# EDU_High-Speed-Design_Power_3V3_1V375.net
KiCad netlist of a schematic drawn in Altium Designer
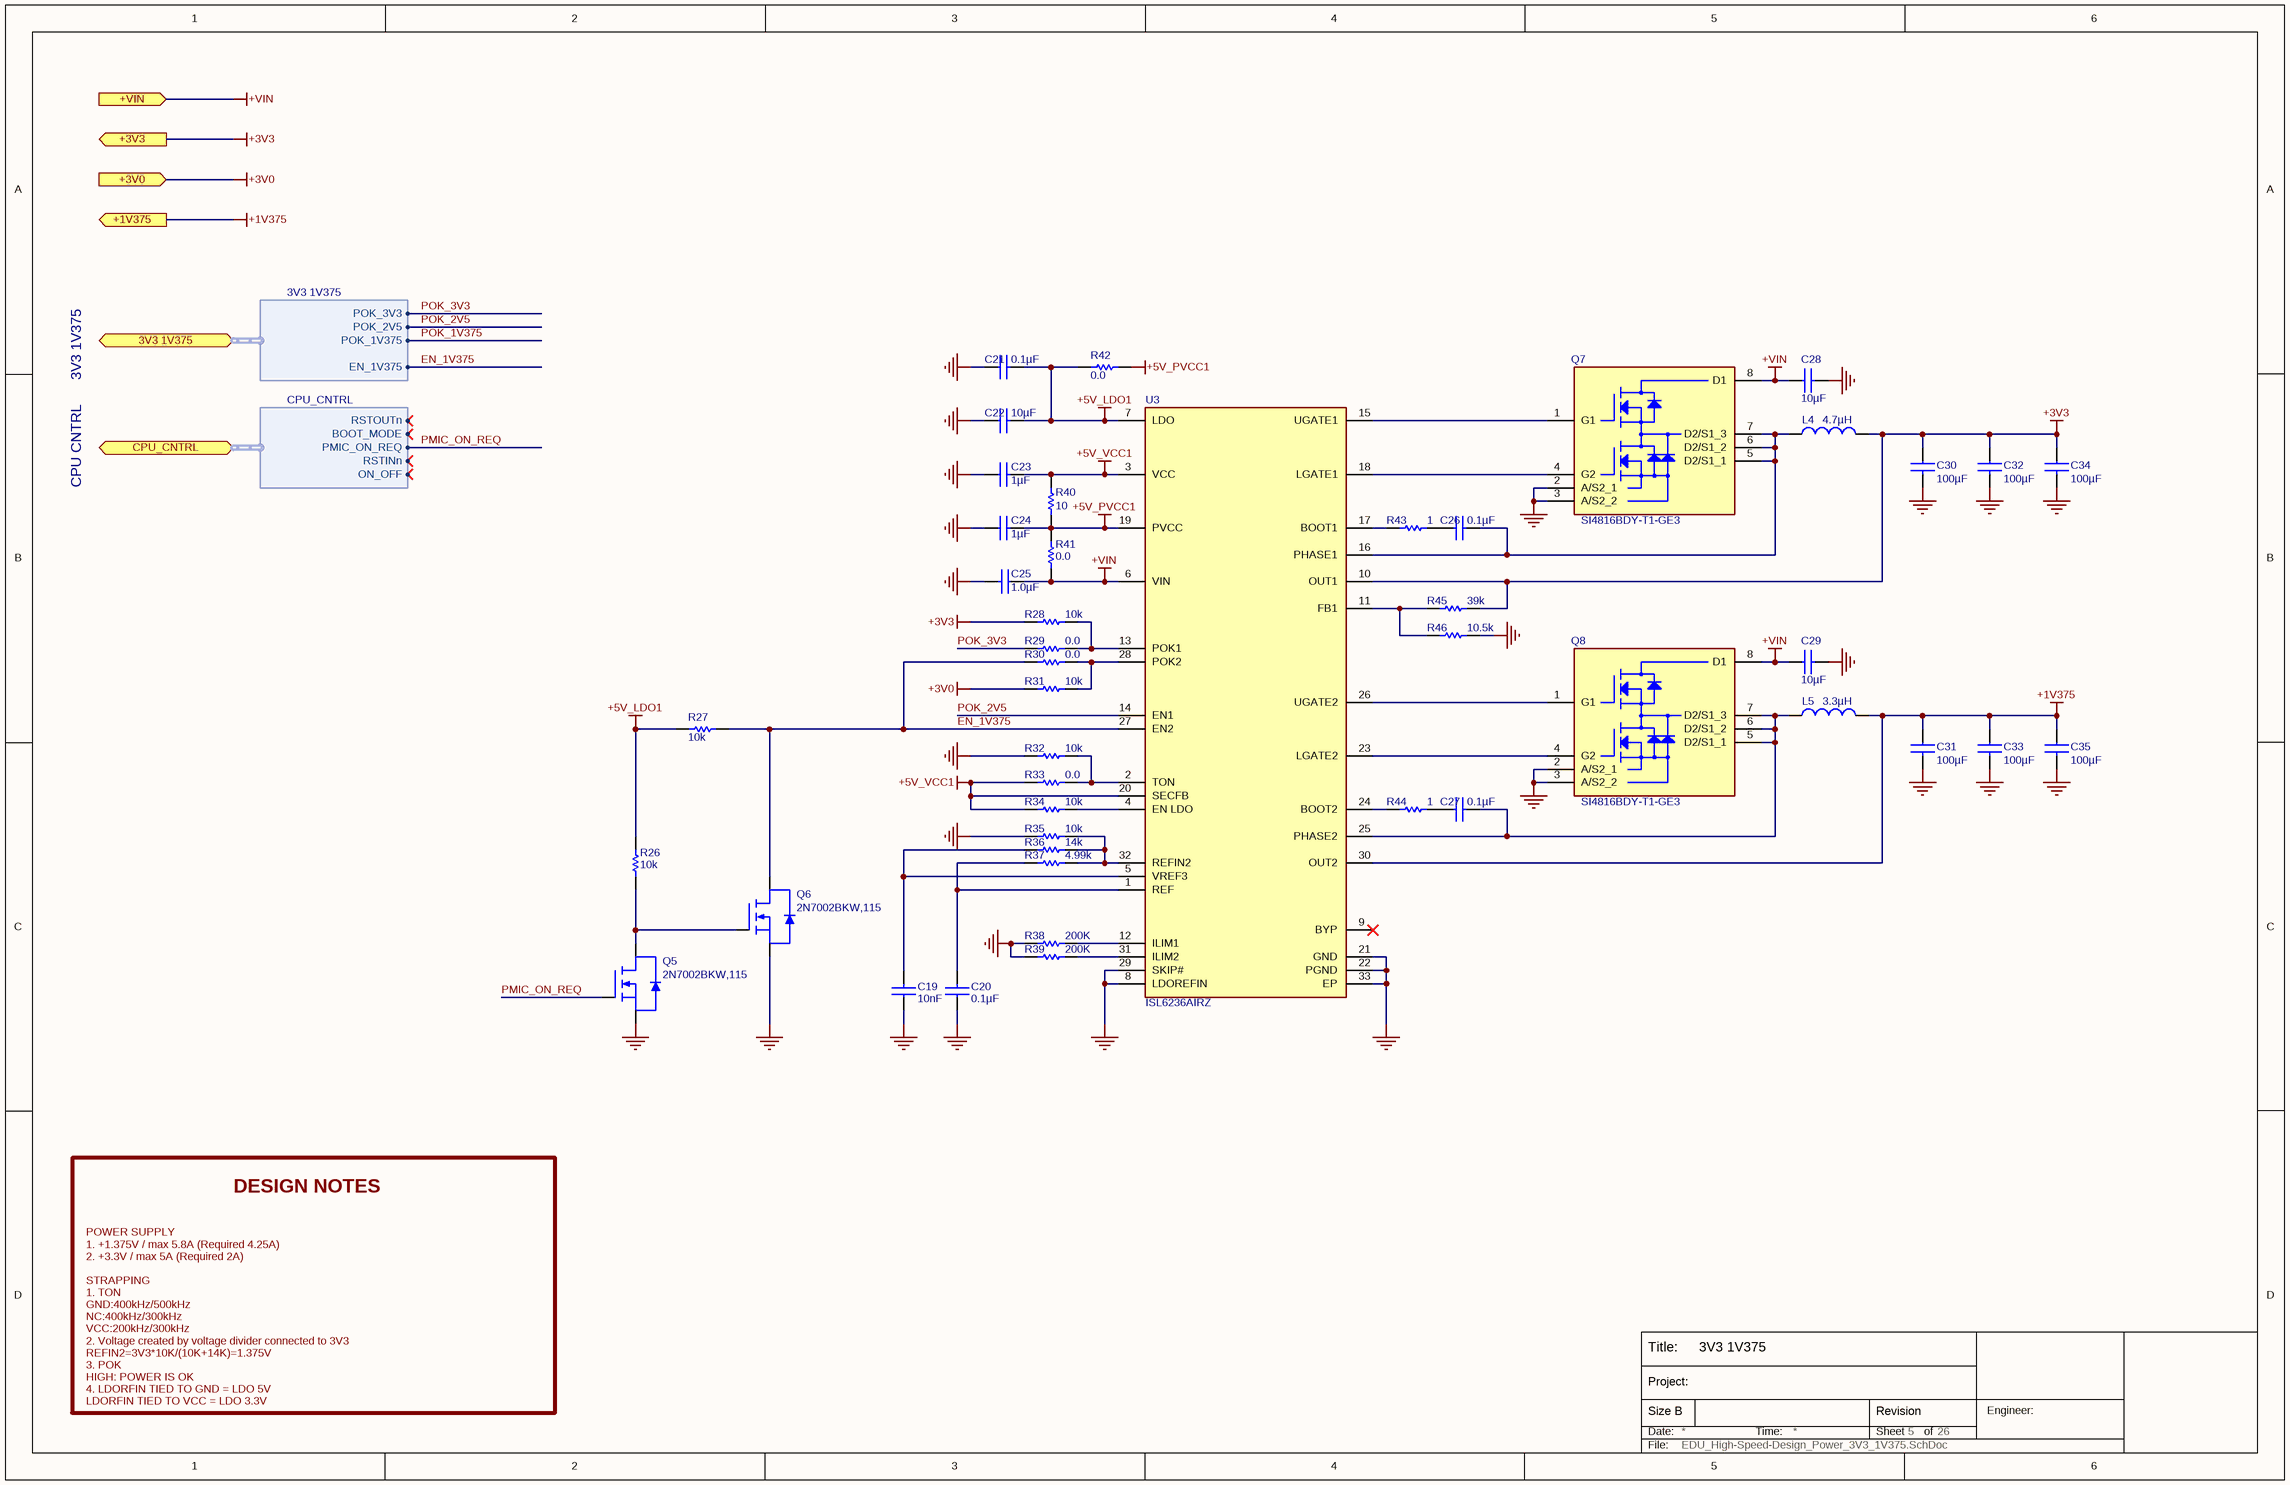
[diagram p0: EDU_High-Speed-Design_Power_3V3_1V375.SchDoc]

(export (version "E")
  (design (tool "Eeschema 10.0.6"))
  (components
    (comp (ref "C19")
      (value "10nF")
      (footprint "C0402")
      (description "CAP CER 10000PF 16V X7R 10% 0402")
      (fields
        (field (name "MANUFACTURER") "TDK Corporation")
        (field (name "MANUFACTURER PART NUMBER") "C1005X7R1C103K")
      )
      (libsource (lib "EDU_High-Speed-Design") (part "C1005X7R1C103K"))
    )
    (comp (ref "C20")
      (value "0.1µF")
      (footprint "C0402")
      (description "CAP CER .10UF 50V X5R 10% 0402")
      (fields (field (name "VOLTAGE") "50V"))
      (libsource (lib "EDU_High-Speed-Design") (part "C1005X5R1H104K"))
    )
    (comp (ref "C21")
      (value "0.1µF")
      (footprint "C0402")
      (description "CAP CER .10UF 50V X5R 10% 0402")
      (fields (field (name "VOLTAGE") "50V"))
      (libsource (lib "EDU_High-Speed-Design") (part "C1005X5R1H104K"))
    )
    (comp (ref "C22")
      (value "10µF")
      (footprint "C0603")
      (description "CAP CER 10UF 6.3V X5R 20% 0603")
      (fields (field (name "VOLTAGE") "6.3V"))
      (libsource (lib "EDU_High-Speed-Design") (part "C1608X5R0J106M"))
    )
    (comp (ref "C23")
      (value "1µF")
      (footprint "C0402")
      (description "CAP CER 1.0UF 16V X5R 0402")
      (fields (field (name "VOLTAGE") "16V"))
      (libsource (lib "EDU_High-Speed-Design") (part "C1005X5R1C105K"))
    )
    (comp (ref "C24")
      (value "1µF")
      (footprint "C0402")
      (description "CAP CER 1.0UF 16V X5R 0402")
      (fields (field (name "VOLTAGE") "16V"))
      (libsource (lib "EDU_High-Speed-Design") (part "C1005X5R1C105K"))
    )
    (comp (ref "C25")
      (value "1.0µF")
      (footprint "C0805")
      (description "CAP CER 1UF 50V X7R 0805")
      (fields (field (name "VOLTAGE") "50V"))
      (libsource (lib "EDU_High-Speed-Design") (part "GRM21BR71H105KA12L"))
    )
    (comp (ref "C26")
      (value "0.1µF")
      (footprint "C0402")
      (description "CAP CER .10UF 50V X5R 10% 0402")
      (fields (field (name "VOLTAGE") "50V"))
      (libsource (lib "EDU_High-Speed-Design") (part "C1005X5R1H104K"))
    )
    (comp (ref "C27")
      (value "0.1µF")
      (footprint "C0402")
      (description "CAP CER .10UF 50V X5R 10% 0402")
      (fields (field (name "VOLTAGE") "50V"))
      (libsource (lib "EDU_High-Speed-Design") (part "C1005X5R1H104K"))
    )
    (comp (ref "C28")
      (value "10µF")
      (footprint "C1206")
      (description "CAP CER 10UF 35V X5R 1206")
      (fields (field (name "VOLTAGE") "35V"))
      (libsource (lib "EDU_High-Speed-Design") (part "GRM31CR6YA106KA12L"))
    )
    (comp (ref "C29")
      (value "10µF")
      (footprint "C1206")
      (description "CAP CER 10UF 35V X5R 1206")
      (fields (field (name "VOLTAGE") "35V"))
      (libsource (lib "EDU_High-Speed-Design") (part "GRM31CR6YA106KA12L"))
    )
    (comp (ref "C30")
      (value "100µF")
      (footprint "C1206")
      (description "CAP CER 100UF 10V X5R 20% 1206")
      (fields (field (name "VOLTAGE") "10V"))
      (libsource (lib "EDU_High-Speed-Design") (part "C3216X5R1A107M"))
    )
    (comp (ref "C31")
      (value "100µF")
      (footprint "C1206")
      (description "CAP CER 100UF 10V X5R 20% 1206")
      (fields (field (name "VOLTAGE") "10V"))
      (libsource (lib "EDU_High-Speed-Design") (part "C3216X5R1A107M"))
    )
    (comp (ref "C32")
      (value "100µF")
      (footprint "C1206")
      (description "CAP CER 100UF 10V X5R 20% 1206")
      (fields (field (name "VOLTAGE") "10V"))
      (libsource (lib "EDU_High-Speed-Design") (part "C3216X5R1A107M"))
    )
    (comp (ref "C33")
      (value "100µF")
      (footprint "C1206")
      (description "CAP CER 100UF 10V X5R 20% 1206")
      (fields (field (name "VOLTAGE") "10V"))
      (libsource (lib "EDU_High-Speed-Design") (part "C3216X5R1A107M"))
    )
    (comp (ref "C34")
      (value "100µF")
      (footprint "C1206")
      (description "CAP CER 100UF 10V X5R 20% 1206")
      (fields (field (name "VOLTAGE") "10V"))
      (libsource (lib "EDU_High-Speed-Design") (part "C3216X5R1A107M"))
    )
    (comp (ref "C35")
      (value "100µF")
      (footprint "C1206")
      (description "CAP CER 100UF 10V X5R 20% 1206")
      (fields (field (name "VOLTAGE") "10V"))
      (libsource (lib "EDU_High-Speed-Design") (part "C3216X5R1A107M"))
    )
    (comp (ref "L4")
      (value "4.7µH")
      (footprint "IHLP2525")
      (description "INDUCTOR POWER 4.7UH 5.5A SMD")
      (libsource (lib "EDU_High-Speed-Design") (part "IHLP2525CZER4R7M01"))
    )
    (comp (ref "L5")
      (value "3.3µH")
      (footprint "IHLP2525")
      (description "INDUCTOR POWER 3.3UH 6A SMD")
      (libsource (lib "EDU_High-Speed-Design") (part "IHLP2525CZER3R3M01"))
    )
    (comp (ref "Q5")
      (value "2N7002BKW,115")
      (footprint "SOT-23-3")
      (description "MOSFET N-CH 60V 310MA SOT323")
      (libsource (lib "EDU_High-Speed-Design") (part "2N7002BKW,115"))
    )
    (comp (ref "Q6")
      (value "2N7002BKW,115")
      (footprint "SOT-23-3")
      (description "MOSFET N-CH 60V 310MA SOT323")
      (libsource (lib "EDU_High-Speed-Design") (part "2N7002BKW,115"))
    )
    (comp (ref "Q7")
      (value "SI4816BDY-T1-GE3")
      (footprint "SO8")
      (description "MOSFET DL N-CH 30V 6.8A 8-SOIC")
      (libsource (lib "EDU_High-Speed-Design") (part "SI4816BDY-T1-GE3"))
    )
    (comp (ref "Q8")
      (value "SI4816BDY-T1-GE3")
      (footprint "SO8")
      (description "MOSFET DL N-CH 30V 6.8A 8-SOIC")
      (libsource (lib "EDU_High-Speed-Design") (part "SI4816BDY-T1-GE3"))
    )
    (comp (ref "R26")
      (value "10k")
      (footprint "R0402")
      (description "RES 10.0K OHM 1/16W 1% 0402 SMD")
      (libsource (lib "EDU_High-Speed-Design") (part "RC0402FR-0710KL"))
    )
    (comp (ref "R27")
      (value "10k")
      (footprint "R0402")
      (description "RES 10.0K OHM 1/16W 1% 0402 SMD")
      (libsource (lib "EDU_High-Speed-Design") (part "RC0402FR-0710KL"))
    )
    (comp (ref "R28")
      (value "10k")
      (footprint "R0402")
      (description "RES 10.0K OHM 1/16W 1% 0402 SMD")
      (libsource (lib "EDU_High-Speed-Design") (part "RC0402FR-0710KL"))
    )
    (comp (ref "R29")
      (value "0.0")
      (footprint "R0402")
      (description "RES 0.0 OHM 1/16W 0402 SMD")
      (libsource (lib "EDU_High-Speed-Design") (part "RC0402JR-070RL"))
    )
    (comp (ref "R30")
      (value "0.0")
      (footprint "R0402")
      (description "RES 0.0 OHM 1/16W 0402 SMD")
      (libsource (lib "EDU_High-Speed-Design") (part "RC0402JR-070RL"))
    )
    (comp (ref "R31")
      (value "10k")
      (footprint "R0402")
      (description "RES 10.0K OHM 1/16W 1% 0402 SMD")
      (libsource (lib "EDU_High-Speed-Design") (part "RC0402FR-0710KL"))
    )
    (comp (ref "R32")
      (value "10k")
      (footprint "R0402")
      (description "RES 10.0K OHM 1/16W 1% 0402 SMD")
      (libsource (lib "EDU_High-Speed-Design") (part "RC0402FR-0710KL"))
    )
    (comp (ref "R33")
      (value "0.0")
      (footprint "R0402")
      (description "RES 0.0 OHM 1/16W 0402 SMD")
      (libsource (lib "EDU_High-Speed-Design") (part "RC0402JR-070RL"))
    )
    (comp (ref "R34")
      (value "10k")
      (footprint "R0402")
      (description "RES 10.0K OHM 1/16W 1% 0402 SMD")
      (libsource (lib "EDU_High-Speed-Design") (part "RC0402FR-0710KL"))
    )
    (comp (ref "R35")
      (value "10k")
      (footprint "R0402")
      (description "RES 10.0K OHM 1/16W 1% 0402 SMD")
      (libsource (lib "EDU_High-Speed-Design") (part "RC0402FR-0710KL"))
    )
    (comp (ref "R36")
      (value "14k")
      (footprint "R0402")
      (description "RES 14.0K OHM 1/16W 1% 0402 SMD")
      (libsource (lib "EDU_High-Speed-Design") (part "RC0402FR-0714KL"))
    )
    (comp (ref "R37")
      (value "4.99k")
      (footprint "R0402")
      (description "RES TF 4.99K OHM 1% 1/16W 0402")
      (libsource (lib "EDU_High-Speed-Design") (part "RMCF0402FT4K99"))
    )
    (comp (ref "R38")
      (value "200K")
      (footprint "R0402")
      (description "RES 200K OHM 1/16W 1% 0402 SMD")
      (libsource (lib "EDU_High-Speed-Design") (part "RC0402FR-07200KL"))
    )
    (comp (ref "R39")
      (value "200K")
      (footprint "R0402")
      (description "RES 200K OHM 1/16W 1% 0402 SMD")
      (libsource (lib "EDU_High-Speed-Design") (part "RC0402FR-07200KL"))
    )
    (comp (ref "R40")
      (value "10")
      (footprint "R0402")
      (description "RES 10.0 OHM 1/16W 1% 0402 SMD")
      (libsource (lib "EDU_High-Speed-Design") (part "RC0402FR-0710RL"))
    )
    (comp (ref "R41")
      (value "0.0")
      (footprint "R0402")
      (description "RES 0.0 OHM 1/16W 0402 SMD")
      (libsource (lib "EDU_High-Speed-Design") (part "RC0402JR-070RL"))
    )
    (comp (ref "R42")
      (value "0.0")
      (footprint "R0402")
      (description "RES 0.0 OHM 1/16W 0402 SMD")
      (libsource (lib "EDU_High-Speed-Design") (part "RC0402JR-070RL"))
    )
    (comp (ref "R43")
      (value "1")
      (footprint "R0402")
      (description "RES 1.00 OHM 1/16W 1% 0402 SM")
      (libsource (lib "EDU_High-Speed-Design") (part "RC0402FR-071RL"))
    )
    (comp (ref "R44")
      (value "1")
      (footprint "R0402")
      (description "RES 1.00 OHM 1/16W 1% 0402 SM")
      (libsource (lib "EDU_High-Speed-Design") (part "RC0402FR-071RL"))
    )
    (comp (ref "R45")
      (value "39k")
      (footprint "R0402")
      (description "RES 39.0K OHM 1/16W 1% 0402 SMD")
      (libsource (lib "EDU_High-Speed-Design") (part "RC0402FR-0739KL"))
    )
    (comp (ref "R46")
      (value "10.5k")
      (footprint "R0402")
      (description "RES 10.5K OHM 1/16W 1% 0402 SMD")
      (libsource (lib "EDU_High-Speed-Design") (part "CRCW040210K5FKED"))
    )
    (comp (ref "U3")
      (value "ISL6236AIRZ")
      (footprint "ISL6236AIRZ")
      (description "IC MAIN PWR CTRLR QUAD 32-QFN")
      (libsource (lib "EDU_High-Speed-Design") (part "ISL6236AIRZ"))
    )
  )
  (nets
    (net (code "4") (name "+1V375") (class "Default")
      (node (ref "C31") (pin "1") (pinfunction "1_1") (pintype "passive"))
      (node (ref "C33") (pin "1") (pinfunction "1_1") (pintype "passive"))
      (node (ref "C35") (pin "1") (pinfunction "1_1") (pintype "passive"))
      (node (ref "L5") (pin "2") (pinfunction "2_2") (pintype "passive"))
      (node (ref "U3") (pin "30") (pinfunction "OUT2_30") (pintype "passive"))
    )
    (net (code "5") (name "+3V0") (class "Default")
      (node (ref "R31") (pin "2") (pinfunction "2_2") (pintype "passive"))
    )
    (net (code "6") (name "+3V3") (class "Default")
      (node (ref "C30") (pin "1") (pinfunction "1_1") (pintype "passive"))
      (node (ref "C32") (pin "1") (pinfunction "1_1") (pintype "passive"))
      (node (ref "C34") (pin "1") (pinfunction "1_1") (pintype "passive"))
      (node (ref "L4") (pin "2") (pinfunction "2_2") (pintype "passive"))
      (node (ref "R28") (pin "2") (pinfunction "2_2") (pintype "passive"))
      (node (ref "R45") (pin "1") (pinfunction "1_1") (pintype "passive"))
      (node (ref "U3") (pin "10") (pinfunction "OUT1_10") (pintype "passive"))
    )
    (net (code "7") (name "+5V_LDO1") (class "Default")
      (node (ref "C21") (pin "2") (pinfunction "2_2") (pintype "passive"))
      (node (ref "C22") (pin "2") (pinfunction "2_2") (pintype "passive"))
      (node (ref "R26") (pin "2") (pinfunction "2_2") (pintype "passive"))
      (node (ref "R27") (pin "2") (pinfunction "2_2") (pintype "passive"))
      (node (ref "R42") (pin "1") (pinfunction "1_1") (pintype "passive"))
      (node (ref "U3") (pin "7") (pinfunction "LDO_7") (pintype "passive"))
    )
    (net (code "8") (name "+5V_PVCC1") (class "Default")
      (node (ref "C24") (pin "2") (pinfunction "2_2") (pintype "passive"))
      (node (ref "R40") (pin "2") (pinfunction "2_2") (pintype "passive"))
      (node (ref "R41") (pin "1") (pinfunction "1_1") (pintype "passive"))
      (node (ref "R42") (pin "2") (pinfunction "2_2") (pintype "passive"))
      (node (ref "U3") (pin "19") (pinfunction "PVCC_19") (pintype "passive"))
    )
    (net (code "9") (name "+5V_VCC1") (class "Default")
      (node (ref "C23") (pin "2") (pinfunction "2_2") (pintype "passive"))
      (node (ref "R33") (pin "2") (pinfunction "2_2") (pintype "passive"))
      (node (ref "R34") (pin "2") (pinfunction "2_2") (pintype "passive"))
      (node (ref "R40") (pin "1") (pinfunction "1_1") (pintype "passive"))
      (node (ref "U3") (pin "20") (pinfunction "SECFB_20") (pintype "passive"))
      (node (ref "U3") (pin "3") (pinfunction "VCC_3") (pintype "passive"))
    )
    (net (code "10") (name "+VIN") (class "Default")
      (node (ref "C25") (pin "1") (pinfunction "1_1") (pintype "passive"))
      (node (ref "C28") (pin "1") (pinfunction "1_1") (pintype "passive"))
      (node (ref "C29") (pin "1") (pinfunction "1_1") (pintype "passive"))
      (node (ref "Q7") (pin "8") (pinfunction "D1_8") (pintype "passive"))
      (node (ref "Q8") (pin "8") (pinfunction "D1_8") (pintype "passive"))
      (node (ref "R41") (pin "2") (pinfunction "2_2") (pintype "passive"))
      (node (ref "U3") (pin "6") (pinfunction "VIN_6") (pintype "passive"))
    )
    (net (code "11") (name "/EN_1V375") (class "Default")
      (node (ref "Q6") (pin "3") (pinfunction "D_3") (pintype "passive"))
      (node (ref "R27") (pin "1") (pinfunction "1_1") (pintype "passive"))
      (node (ref "R30") (pin "2") (pinfunction "2_2") (pintype "passive"))
      (node (ref "U3") (pin "27") (pinfunction "EN2_27") (pintype "passive"))
    )
    (net (code "12") (name "/PMIC_ON_REQ") (class "Default")
      (node (ref "Q5") (pin "1") (pinfunction "G_1") (pintype "passive"))
    )
    (net (code "14") (name "/POK_2V5") (class "Default")
      (node (ref "U3") (pin "14") (pinfunction "EN1_14") (pintype "passive"))
    )
    (net (code "15") (name "/POK_3V3") (class "Default")
      (node (ref "R29") (pin "2") (pinfunction "2_2") (pintype "passive"))
    )
    (net (code "18") (name "GND") (class "Default")
      (node (ref "C19") (pin "1") (pinfunction "1_1") (pintype "passive"))
      (node (ref "C20") (pin "1") (pinfunction "1_1") (pintype "passive"))
      (node (ref "C21") (pin "1") (pinfunction "1_1") (pintype "passive"))
      (node (ref "C22") (pin "1") (pinfunction "1_1") (pintype "passive"))
      (node (ref "C23") (pin "1") (pinfunction "1_1") (pintype "passive"))
      (node (ref "C24") (pin "1") (pinfunction "1_1") (pintype "passive"))
      (node (ref "C25") (pin "2") (pinfunction "2_2") (pintype "passive"))
      (node (ref "C28") (pin "2") (pinfunction "2_2") (pintype "passive"))
      (node (ref "C29") (pin "2") (pinfunction "2_2") (pintype "passive"))
      (node (ref "C30") (pin "2") (pinfunction "2_2") (pintype "passive"))
      (node (ref "C31") (pin "2") (pinfunction "2_2") (pintype "passive"))
      (node (ref "C32") (pin "2") (pinfunction "2_2") (pintype "passive"))
      (node (ref "C33") (pin "2") (pinfunction "2_2") (pintype "passive"))
      (node (ref "C34") (pin "2") (pinfunction "2_2") (pintype "passive"))
      (node (ref "C35") (pin "2") (pinfunction "2_2") (pintype "passive"))
      (node (ref "Q5") (pin "2") (pinfunction "S_2") (pintype "passive"))
      (node (ref "Q6") (pin "2") (pinfunction "S_2") (pintype "passive"))
      (node (ref "Q7") (pin "2") (pinfunction "A/S2_1_2") (pintype "passive"))
      (node (ref "Q7") (pin "3") (pinfunction "A/S2_2_3") (pintype "passive"))
      (node (ref "Q8") (pin "2") (pinfunction "A/S2_1_2") (pintype "passive"))
      (node (ref "Q8") (pin "3") (pinfunction "A/S2_2_3") (pintype "passive"))
      (node (ref "R32") (pin "2") (pinfunction "2_2") (pintype "passive"))
      (node (ref "R35") (pin "2") (pinfunction "2_2") (pintype "passive"))
      (node (ref "R38") (pin "2") (pinfunction "2_2") (pintype "passive"))
      (node (ref "R39") (pin "2") (pinfunction "2_2") (pintype "passive"))
      (node (ref "R46") (pin "1") (pinfunction "1_1") (pintype "passive"))
      (node (ref "U3") (pin "21") (pinfunction "GND_21") (pintype "passive"))
      (node (ref "U3") (pin "22") (pinfunction "PGND_22") (pintype "passive"))
      (node (ref "U3") (pin "29") (pinfunction "SKIP#_29") (pintype "passive"))
      (node (ref "U3") (pin "33") (pinfunction "EP_33") (pintype "passive"))
      (node (ref "U3") (pin "8") (pinfunction "LDOREFIN_8") (pintype "passive"))
    )
    (net (code "19") (name "Net-(C26-Pad1)") (class "Default")
      (node (ref "C26") (pin "1") (pinfunction "1_1") (pintype "passive"))
      (node (ref "R43") (pin "1") (pinfunction "1_1") (pintype "passive"))
    )
    (net (code "20") (name "Net-(C27-Pad1)") (class "Default")
      (node (ref "C27") (pin "1") (pinfunction "1_1") (pintype "passive"))
      (node (ref "R44") (pin "1") (pinfunction "1_1") (pintype "passive"))
    )
    (net (code "21") (name "Net-(Q5-D)") (class "Default")
      (node (ref "Q5") (pin "3") (pinfunction "D_3") (pintype "passive"))
      (node (ref "Q6") (pin "1") (pinfunction "G_1") (pintype "passive"))
      (node (ref "R26") (pin "1") (pinfunction "1_1") (pintype "passive"))
    )
    (net (code "22") (name "Net-(Q7-D2{slash}S1_1)") (class "Default")
      (node (ref "C26") (pin "2") (pinfunction "2_2") (pintype "passive"))
      (node (ref "L4") (pin "1") (pinfunction "1_1") (pintype "passive"))
      (node (ref "Q7") (pin "5") (pinfunction "D2/S1_1_5") (pintype "passive"))
      (node (ref "Q7") (pin "6") (pinfunction "D2/S1_2_6") (pintype "passive"))
      (node (ref "Q7") (pin "7") (pinfunction "D2/S1_3_7") (pintype "passive"))
      (node (ref "U3") (pin "16") (pinfunction "PHASE1_16") (pintype "passive"))
    )
    (net (code "23") (name "Net-(Q7-G1)") (class "Default")
      (node (ref "Q7") (pin "1") (pinfunction "G1_1") (pintype "passive"))
      (node (ref "U3") (pin "15") (pinfunction "UGATE1_15") (pintype "passive"))
    )
    (net (code "24") (name "Net-(Q7-G2)") (class "Default")
      (node (ref "Q7") (pin "4") (pinfunction "G2_4") (pintype "passive"))
      (node (ref "U3") (pin "18") (pinfunction "LGATE1_18") (pintype "passive"))
    )
    (net (code "25") (name "Net-(Q8-D2{slash}S1_1)") (class "Default")
      (node (ref "C27") (pin "2") (pinfunction "2_2") (pintype "passive"))
      (node (ref "L5") (pin "1") (pinfunction "1_1") (pintype "passive"))
      (node (ref "Q8") (pin "5") (pinfunction "D2/S1_1_5") (pintype "passive"))
      (node (ref "Q8") (pin "6") (pinfunction "D2/S1_2_6") (pintype "passive"))
      (node (ref "Q8") (pin "7") (pinfunction "D2/S1_3_7") (pintype "passive"))
      (node (ref "U3") (pin "25") (pinfunction "PHASE2_25") (pintype "passive"))
    )
    (net (code "26") (name "Net-(Q8-G1)") (class "Default")
      (node (ref "Q8") (pin "1") (pinfunction "G1_1") (pintype "passive"))
      (node (ref "U3") (pin "26") (pinfunction "UGATE2_26") (pintype "passive"))
    )
    (net (code "27") (name "Net-(Q8-G2)") (class "Default")
      (node (ref "Q8") (pin "4") (pinfunction "G2_4") (pintype "passive"))
      (node (ref "U3") (pin "23") (pinfunction "LGATE2_23") (pintype "passive"))
    )
    (net (code "28") (name "Net-(U3-BOOT1)") (class "Default")
      (node (ref "R43") (pin "2") (pinfunction "2_2") (pintype "passive"))
      (node (ref "U3") (pin "17") (pinfunction "BOOT1_17") (pintype "passive"))
    )
    (net (code "29") (name "Net-(U3-BOOT2)") (class "Default")
      (node (ref "R44") (pin "2") (pinfunction "2_2") (pintype "passive"))
      (node (ref "U3") (pin "24") (pinfunction "BOOT2_24") (pintype "passive"))
    )
    (net (code "30") (name "Net-(U3-EN_LDO)") (class "Default")
      (node (ref "R34") (pin "1") (pinfunction "1_1") (pintype "passive"))
      (node (ref "U3") (pin "4") (pinfunction "EN_LDO_4") (pintype "passive"))
    )
    (net (code "31") (name "Net-(U3-FB1)") (class "Default")
      (node (ref "R45") (pin "2") (pinfunction "2_2") (pintype "passive"))
      (node (ref "R46") (pin "2") (pinfunction "2_2") (pintype "passive"))
      (node (ref "U3") (pin "11") (pinfunction "FB1_11") (pintype "passive"))
    )
    (net (code "32") (name "Net-(U3-ILIM1)") (class "Default")
      (node (ref "R38") (pin "1") (pinfunction "1_1") (pintype "passive"))
      (node (ref "U3") (pin "12") (pinfunction "ILIM1_12") (pintype "passive"))
    )
    (net (code "33") (name "Net-(U3-ILIM2)") (class "Default")
      (node (ref "R39") (pin "1") (pinfunction "1_1") (pintype "passive"))
      (node (ref "U3") (pin "31") (pinfunction "ILIM2_31") (pintype "passive"))
    )
    (net (code "34") (name "Net-(U3-POK1)") (class "Default")
      (node (ref "R28") (pin "1") (pinfunction "1_1") (pintype "passive"))
      (node (ref "R29") (pin "1") (pinfunction "1_1") (pintype "passive"))
      (node (ref "U3") (pin "13") (pinfunction "POK1_13") (pintype "passive"))
    )
    (net (code "35") (name "Net-(U3-POK2)") (class "Default")
      (node (ref "R30") (pin "1") (pinfunction "1_1") (pintype "passive"))
      (node (ref "R31") (pin "1") (pinfunction "1_1") (pintype "passive"))
      (node (ref "U3") (pin "28") (pinfunction "POK2_28") (pintype "passive"))
    )
    (net (code "36") (name "Net-(U3-REF)") (class "Default")
      (node (ref "C20") (pin "2") (pinfunction "2_2") (pintype "passive"))
      (node (ref "R37") (pin "1") (pinfunction "1_1") (pintype "passive"))
      (node (ref "U3") (pin "1") (pinfunction "REF_1") (pintype "passive"))
    )
    (net (code "37") (name "Net-(U3-REFIN2)") (class "Default")
      (node (ref "R35") (pin "1") (pinfunction "1_1") (pintype "passive"))
      (node (ref "R36") (pin "1") (pinfunction "1_1") (pintype "passive"))
      (node (ref "R37") (pin "2") (pinfunction "2_2") (pintype "passive"))
      (node (ref "U3") (pin "32") (pinfunction "REFIN2_32") (pintype "passive"))
    )
    (net (code "38") (name "Net-(U3-TON)") (class "Default")
      (node (ref "R32") (pin "1") (pinfunction "1_1") (pintype "passive"))
      (node (ref "R33") (pin "1") (pinfunction "1_1") (pintype "passive"))
      (node (ref "U3") (pin "2") (pinfunction "TON_2") (pintype "passive"))
    )
    (net (code "39") (name "Net-(U3-VREF3)") (class "Default")
      (node (ref "C19") (pin "2") (pinfunction "2_2") (pintype "passive"))
      (node (ref "R36") (pin "2") (pinfunction "2_2") (pintype "passive"))
      (node (ref "U3") (pin "5") (pinfunction "VREF3_5") (pintype "passive"))
    )
    (net (code "40") (name "unconnected-(U3-BYP-Pad9)") (class "Default")
      (node (ref "U3") (pin "9") (pinfunction "BYP_9") (pintype "passive+no_connect"))
    )
  )
)
